# Filters.net
KiCad netlist of a schematic drawn in Altium Designer
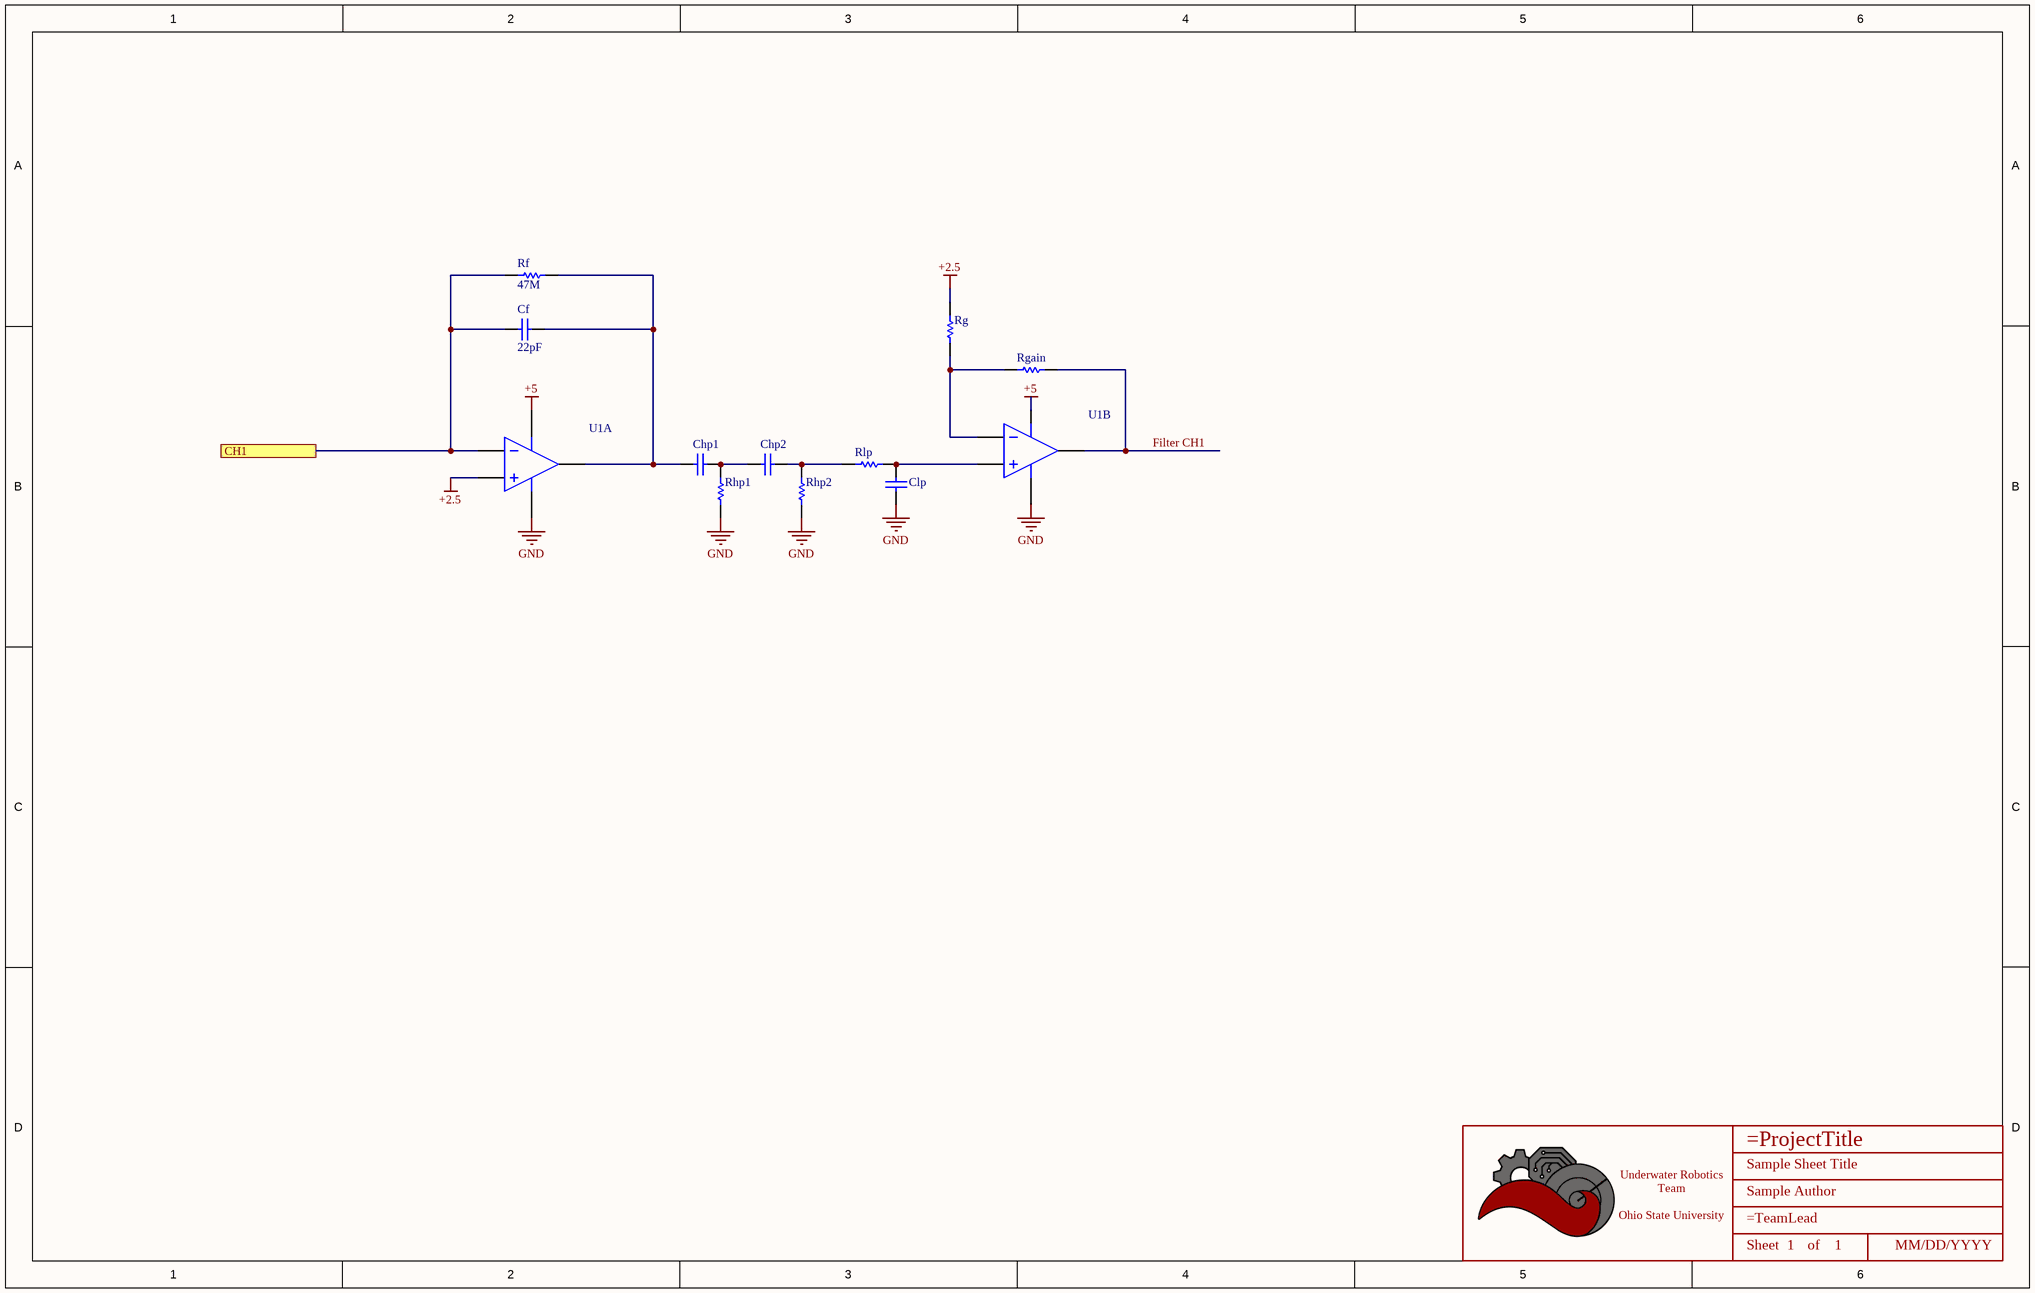
[diagram p0: Filters.SchDoc]

(export (version "E")
  (design (tool "Eeschema 10.0.6"))
  (components
    (comp (ref "*")
      (value "Title_Block")
      (footprint "LOGO")
      (description "UWRT Schematic Title Block Template\r\n\r\nCreated June 2021, Dylan Trainor")
      (libsource (lib "UWRT") (part "Title_Block"))
    )
    (comp (ref "Cf")
      (value "22pF")
      (description "Capacitor")
      (libsource (lib "Simulation Generic Components") (part "Capacitor"))
    )
    (comp (ref "Chp1")
      (value "Capacitor")
      (libsource (lib "Simulation Generic Components") (part "Capacitor"))
    )
    (comp (ref "Chp2")
      (value "Capacitor")
      (libsource (lib "Simulation Generic Components") (part "Capacitor"))
    )
    (comp (ref "Clp")
      (value "Capacitor")
      (libsource (lib "Simulation Generic Components") (part "Capacitor"))
    )
    (comp (ref "Rf")
      (value "47M")
      (description "Resistor")
      (libsource (lib "Simulation Generic Components") (part "Resistor"))
    )
    (comp (ref "Rg") (value "Resistor") (libsource (lib "Simulation Generic Components") (part "Resistor")))
    (comp (ref "Rgain")
      (value "Resistor")
      (libsource (lib "Simulation Generic Components") (part "Resistor"))
    )
    (comp (ref "Rhp1") (value "Resistor") (libsource (lib "Simulation Generic Components") (part "Resistor")))
    (comp (ref "Rhp2") (value "Resistor") (libsource (lib "Simulation Generic Components") (part "Resistor")))
    (comp (ref "Rlp") (value "Resistor") (libsource (lib "Simulation Generic Components") (part "Resistor")))
    (comp (ref "U1A")
      (value "Ideal Operational Amplifier")
      (libsource (lib "Simulation Generic Components") (part "OpAmp with power terminals"))
    )
    (comp (ref "U1B")
      (value "Ideal Operational Amplifier")
      (libsource (lib "Simulation Generic Components") (part "OpAmp with power terminals"))
    )
  )
  (nets
    (net (code "1") (name "+2.5") (class "Default")
      (node (ref "Rg") (pin "2") (pinfunction "2_2") (pintype "passive"))
      (node (ref "U1A") (pin "2") (pinfunction "IN+_2") (pintype "passive"))
    )
    (net (code "2") (name "+5") (class "Default")
      (node (ref "U1A") (pin "4") (pinfunction "V+_4") (pintype "power_in"))
      (node (ref "U1B") (pin "4") (pinfunction "V+_4") (pintype "power_in"))
    )
    (net (code "3") (name "/CH1") (class "Default")
      (node (ref "Cf") (pin "1") (pinfunction "1_1") (pintype "passive"))
      (node (ref "Rf") (pin "1") (pinfunction "1_1") (pintype "passive"))
      (node (ref "U1A") (pin "1") (pinfunction "IN-_1") (pintype "passive"))
    )
    (net (code "4") (name "/Filter CH1") (class "Default")
      (node (ref "Rgain") (pin "2") (pinfunction "2_2") (pintype "passive"))
      (node (ref "U1B") (pin "3") (pinfunction "OUT_3") (pintype "passive"))
    )
    (net (code "5") (name "GND") (class "Default")
      (node (ref "Clp") (pin "1") (pinfunction "1_1") (pintype "passive"))
      (node (ref "Rhp1") (pin "2") (pinfunction "2_2") (pintype "passive"))
      (node (ref "Rhp2") (pin "2") (pinfunction "2_2") (pintype "passive"))
      (node (ref "U1A") (pin "5") (pinfunction "V-_5") (pintype "power_in"))
      (node (ref "U1B") (pin "5") (pinfunction "V-_5") (pintype "power_in"))
    )
    (net (code "6") (name "Net-(Chp1-Pad2)") (class "Default")
      (node (ref "Chp1") (pin "2") (pinfunction "2_2") (pintype "passive"))
      (node (ref "Chp2") (pin "1") (pinfunction "1_1") (pintype "passive"))
      (node (ref "Rhp1") (pin "1") (pinfunction "1_1") (pintype "passive"))
    )
    (net (code "7") (name "Net-(Chp2-Pad2)") (class "Default")
      (node (ref "Chp2") (pin "2") (pinfunction "2_2") (pintype "passive"))
      (node (ref "Rhp2") (pin "1") (pinfunction "1_1") (pintype "passive"))
      (node (ref "Rlp") (pin "1") (pinfunction "1_1") (pintype "passive"))
    )
    (net (code "8") (name "Net-(U1A-OUT)") (class "Default")
      (node (ref "Cf") (pin "2") (pinfunction "2_2") (pintype "passive"))
      (node (ref "Chp1") (pin "1") (pinfunction "1_1") (pintype "passive"))
      (node (ref "Rf") (pin "2") (pinfunction "2_2") (pintype "passive"))
      (node (ref "U1A") (pin "3") (pinfunction "OUT_3") (pintype "passive"))
    )
    (net (code "9") (name "Net-(U1B-IN+)") (class "Default")
      (node (ref "Clp") (pin "2") (pinfunction "2_2") (pintype "passive"))
      (node (ref "Rlp") (pin "2") (pinfunction "2_2") (pintype "passive"))
      (node (ref "U1B") (pin "2") (pinfunction "IN+_2") (pintype "passive"))
    )
    (net (code "10") (name "Net-(U1B-IN-)") (class "Default")
      (node (ref "Rg") (pin "1") (pinfunction "1_1") (pintype "passive"))
      (node (ref "Rgain") (pin "1") (pinfunction "1_1") (pintype "passive"))
      (node (ref "U1B") (pin "1") (pinfunction "IN-_1") (pintype "passive"))
    )
  )
)
